# PLO_v1.net
KiCad netlist of a schematic drawn in EAGLE
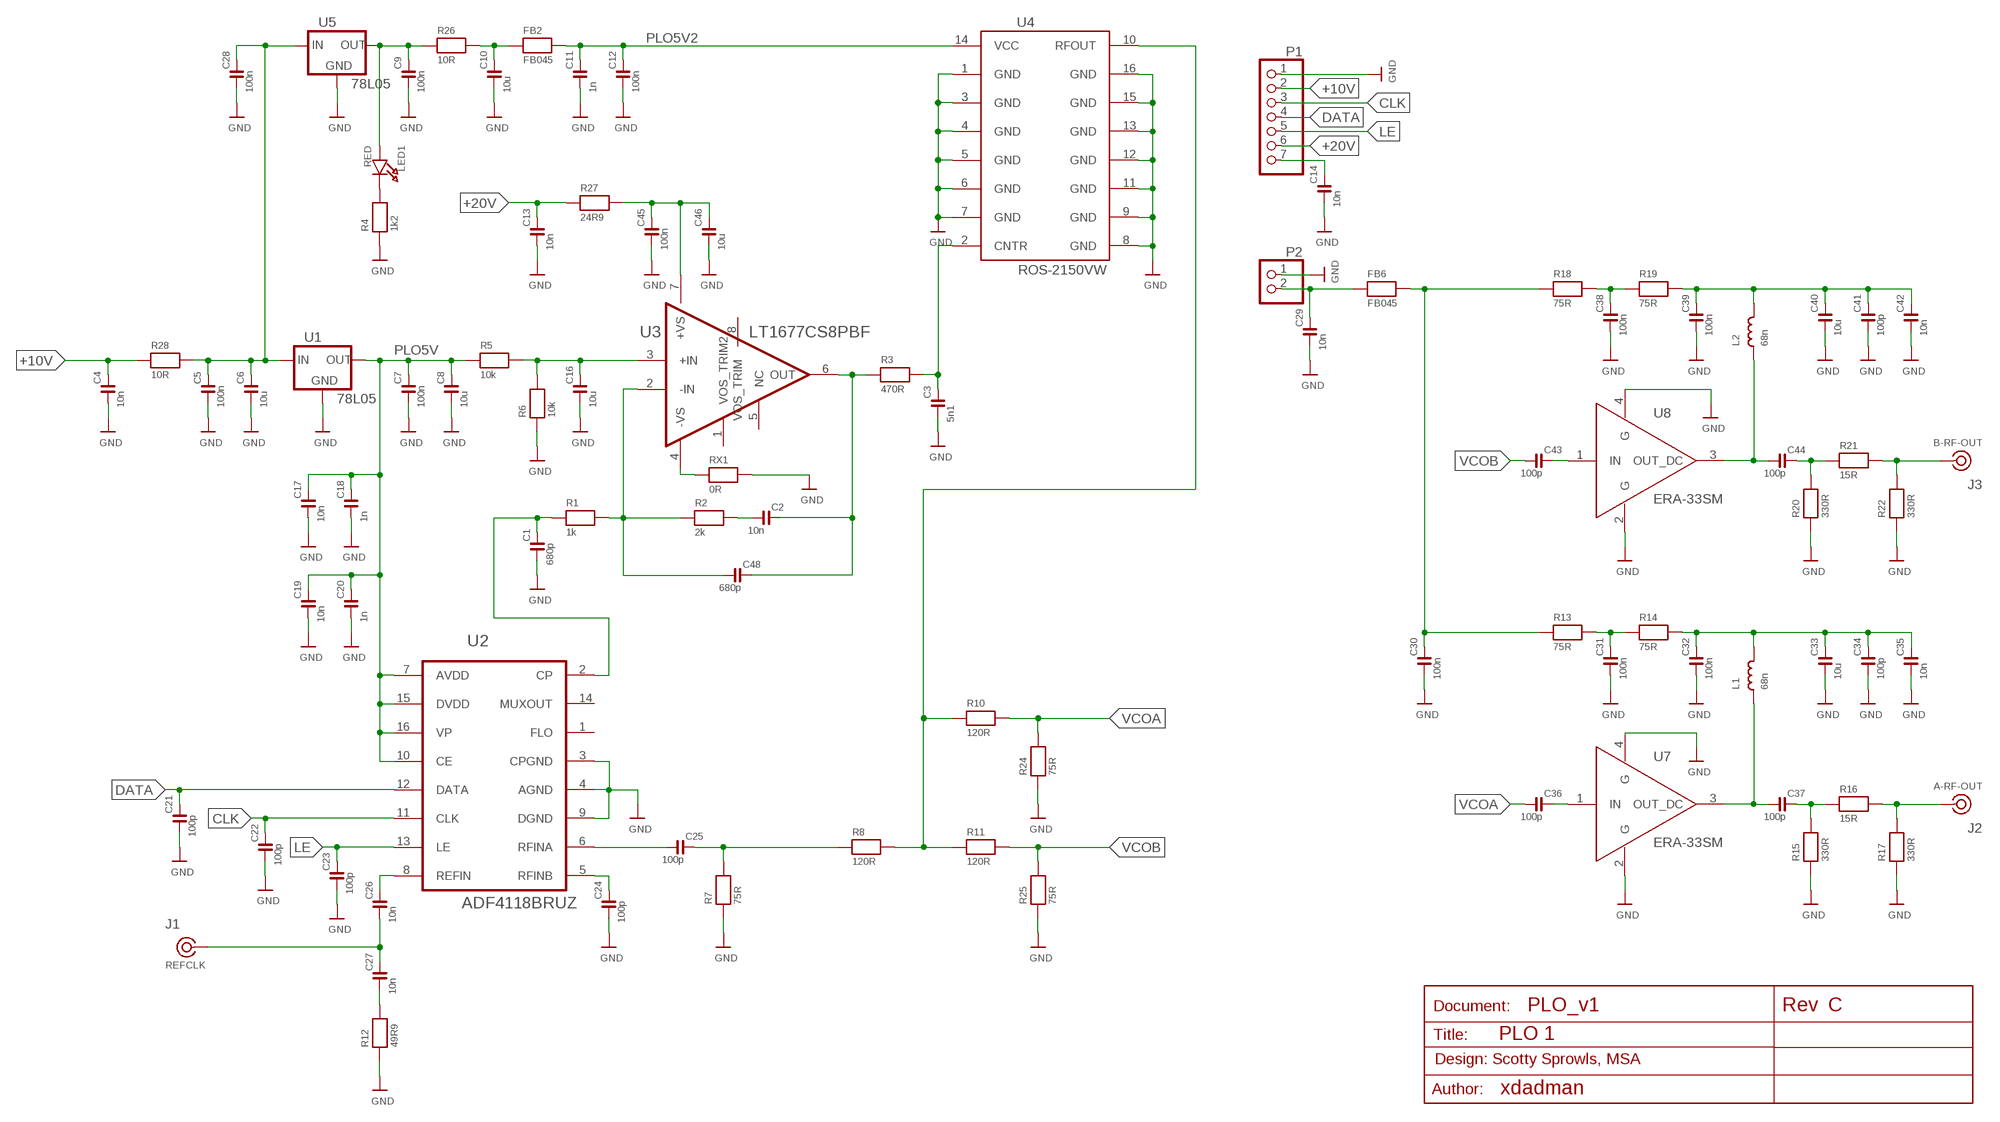
[diagram p0: schematic, sheet 1]

(export (version "E")
  (design (tool "Eeschema 10.0.6"))
  (components
    (comp (ref "C1")
      (value "680p")
      (footprint "eagle-import:C0805")
      (libsource (lib "eagle-import") (part "C0805680P"))
    )
    (comp (ref "C2")
      (value "10n")
      (footprint "eagle-import:C0805")
      (libsource (lib "eagle-import") (part "C080510N"))
    )
    (comp (ref "C3")
      (value "5n1")
      (footprint "eagle-import:C0805")
      (libsource (lib "eagle-import") (part "C08055N1"))
    )
    (comp (ref "C4")
      (value "10n")
      (footprint "eagle-import:C0805")
      (libsource (lib "eagle-import") (part "C080510N"))
    )
    (comp (ref "C5")
      (value "100n")
      (footprint "eagle-import:C0805")
      (libsource (lib "eagle-import") (part "C0805100N"))
    )
    (comp (ref "C6")
      (value "10u")
      (footprint "eagle-import:C1206")
      (libsource (lib "eagle-import") (part "CC120610U"))
    )
    (comp (ref "C7")
      (value "100n")
      (footprint "eagle-import:C0805")
      (libsource (lib "eagle-import") (part "C0805100N"))
    )
    (comp (ref "C8")
      (value "10u")
      (footprint "eagle-import:C1206")
      (libsource (lib "eagle-import") (part "CC120610U"))
    )
    (comp (ref "C9")
      (value "100n")
      (footprint "eagle-import:C0805")
      (libsource (lib "eagle-import") (part "C0805100N"))
    )
    (comp (ref "C10")
      (value "10u")
      (footprint "eagle-import:C1206")
      (libsource (lib "eagle-import") (part "CC120610U"))
    )
    (comp (ref "C11")
      (value "1n")
      (footprint "eagle-import:C0805")
      (libsource (lib "eagle-import") (part "C08051N"))
    )
    (comp (ref "C12")
      (value "100n")
      (footprint "eagle-import:C0805")
      (libsource (lib "eagle-import") (part "C0805100N"))
    )
    (comp (ref "C13")
      (value "10n")
      (footprint "eagle-import:C0805")
      (libsource (lib "eagle-import") (part "C080510N"))
    )
    (comp (ref "C14")
      (value "10n")
      (footprint "eagle-import:C0805")
      (libsource (lib "eagle-import") (part "C080510N"))
    )
    (comp (ref "C16")
      (value "10u")
      (footprint "eagle-import:C1206")
      (libsource (lib "eagle-import") (part "CC120610U"))
    )
    (comp (ref "C17")
      (value "10n")
      (footprint "eagle-import:C0805")
      (libsource (lib "eagle-import") (part "C080510N"))
    )
    (comp (ref "C18")
      (value "1n")
      (footprint "eagle-import:C0805")
      (libsource (lib "eagle-import") (part "C08051N"))
    )
    (comp (ref "C19")
      (value "10n")
      (footprint "eagle-import:C0805")
      (libsource (lib "eagle-import") (part "C080510N"))
    )
    (comp (ref "C20")
      (value "1n")
      (footprint "eagle-import:C0805")
      (libsource (lib "eagle-import") (part "C08051N"))
    )
    (comp (ref "C21")
      (value "100p")
      (footprint "eagle-import:C0805")
      (libsource (lib "eagle-import") (part "C0805100P"))
    )
    (comp (ref "C22")
      (value "100p")
      (footprint "eagle-import:C0805")
      (libsource (lib "eagle-import") (part "C0805100P"))
    )
    (comp (ref "C23")
      (value "100p")
      (footprint "eagle-import:C0805")
      (libsource (lib "eagle-import") (part "C0805100P"))
    )
    (comp (ref "C24")
      (value "100p")
      (footprint "eagle-import:C0805")
      (libsource (lib "eagle-import") (part "C0805100P"))
    )
    (comp (ref "C25")
      (value "100p")
      (footprint "eagle-import:C0805")
      (libsource (lib "eagle-import") (part "C0805100P"))
    )
    (comp (ref "C26")
      (value "10n")
      (footprint "eagle-import:C0805")
      (libsource (lib "eagle-import") (part "C080510N"))
    )
    (comp (ref "C27")
      (value "10n")
      (footprint "eagle-import:C0805")
      (libsource (lib "eagle-import") (part "C080510N"))
    )
    (comp (ref "C28")
      (value "100n")
      (footprint "eagle-import:C0805")
      (libsource (lib "eagle-import") (part "C0805100N"))
    )
    (comp (ref "C29")
      (value "10n")
      (footprint "eagle-import:C0805")
      (libsource (lib "eagle-import") (part "C080510N"))
    )
    (comp (ref "C30")
      (value "100n")
      (footprint "eagle-import:C0805")
      (libsource (lib "eagle-import") (part "C0805100N"))
    )
    (comp (ref "C31")
      (value "100n")
      (footprint "eagle-import:C0805")
      (libsource (lib "eagle-import") (part "C0805100N"))
    )
    (comp (ref "C32")
      (value "100n")
      (footprint "eagle-import:C0805")
      (libsource (lib "eagle-import") (part "C0805100N"))
    )
    (comp (ref "C33")
      (value "10u")
      (footprint "eagle-import:C1206")
      (libsource (lib "eagle-import") (part "CC120610U"))
    )
    (comp (ref "C34")
      (value "100p")
      (footprint "eagle-import:C0805")
      (libsource (lib "eagle-import") (part "C0805100P"))
    )
    (comp (ref "C35")
      (value "10n")
      (footprint "eagle-import:C0805")
      (libsource (lib "eagle-import") (part "C080510N"))
    )
    (comp (ref "C36")
      (value "100p")
      (footprint "eagle-import:C0805")
      (libsource (lib "eagle-import") (part "C0805100P"))
    )
    (comp (ref "C37")
      (value "100p")
      (footprint "eagle-import:C0805")
      (libsource (lib "eagle-import") (part "C0805100P"))
    )
    (comp (ref "C38")
      (value "100n")
      (footprint "eagle-import:C0805")
      (libsource (lib "eagle-import") (part "C0805100N"))
    )
    (comp (ref "C39")
      (value "100n")
      (footprint "eagle-import:C0805")
      (libsource (lib "eagle-import") (part "C0805100N"))
    )
    (comp (ref "C40")
      (value "10u")
      (footprint "eagle-import:C1206")
      (libsource (lib "eagle-import") (part "CC120610U"))
    )
    (comp (ref "C41")
      (value "100p")
      (footprint "eagle-import:C0805")
      (libsource (lib "eagle-import") (part "C0805100P"))
    )
    (comp (ref "C42")
      (value "10n")
      (footprint "eagle-import:C0805")
      (libsource (lib "eagle-import") (part "C080510N"))
    )
    (comp (ref "C43")
      (value "100p")
      (footprint "eagle-import:C0805")
      (libsource (lib "eagle-import") (part "C0805100P"))
    )
    (comp (ref "C44")
      (value "100p")
      (footprint "eagle-import:C0805")
      (libsource (lib "eagle-import") (part "C0805100P"))
    )
    (comp (ref "C45")
      (value "100n")
      (footprint "eagle-import:C0805")
      (libsource (lib "eagle-import") (part "C0805100N"))
    )
    (comp (ref "C46")
      (value "10u")
      (footprint "eagle-import:C1206")
      (libsource (lib "eagle-import") (part "CC120610U"))
    )
    (comp (ref "C48")
      (value "680p")
      (footprint "eagle-import:C0805")
      (libsource (lib "eagle-import") (part "C0805680P"))
    )
    (comp (ref "FB2")
      (value "FB045")
      (footprint "eagle-import:R0805_SPC")
      (libsource (lib "eagle-import") (part "R0805FB045SPC"))
    )
    (comp (ref "FB6")
      (value "FB045")
      (footprint "eagle-import:R0805")
      (libsource (lib "eagle-import") (part "R0805FB045"))
    )
    (comp (ref "J1")
      (value "REFCLK")
      (footprint "eagle-import:SLIM_COAX_PAD")
      (libsource (lib "eagle-import") (part "COAX"))
    )
    (comp (ref "J2")
      (value "A-RF-OUT")
      (footprint "eagle-import:SLIM_COAX_PAD")
      (libsource (lib "eagle-import") (part "COAX"))
    )
    (comp (ref "J3")
      (value "B-RF-OUT")
      (footprint "eagle-import:SLIM_COAX_PAD")
      (libsource (lib "eagle-import") (part "COAX"))
    )
    (comp (ref "L1")
      (value "68n")
      (footprint "eagle-import:0603-MINI")
      (libsource (lib "eagle-import") (part "L060368N"))
    )
    (comp (ref "L2")
      (value "68n")
      (footprint "eagle-import:0603-MINI")
      (libsource (lib "eagle-import") (part "L060368N"))
    )
    (comp (ref "LED1")
      (value "RED")
      (footprint "eagle-import:CHIPLED_0603")
      (libsource (lib "eagle-import") (part "LED_0603_RED0603"))
    )
    (comp (ref "P1")
      (value "PINHD-1X7")
      (footprint "eagle-import:1X07")
      (libsource (lib "eagle-import") (part "PINHD-1X7"))
    )
    (comp (ref "P2")
      (value "PINHD-1X2")
      (footprint "eagle-import:1X02")
      (libsource (lib "eagle-import") (part "PINHD-1X2"))
    )
    (comp (ref "R1")
      (value "1k")
      (footprint "eagle-import:R0805")
      (libsource (lib "eagle-import") (part "R08051K"))
    )
    (comp (ref "R2")
      (value "2k")
      (footprint "eagle-import:C0805")
      (libsource (lib "eagle-import") (part "R08052K"))
    )
    (comp (ref "R3")
      (value "470R")
      (footprint "eagle-import:R0805")
      (libsource (lib "eagle-import") (part "R0805470R"))
    )
    (comp (ref "R4")
      (value "1k2")
      (footprint "eagle-import:R0805")
      (libsource (lib "eagle-import") (part "R08051K2"))
    )
    (comp (ref "R5")
      (value "10k")
      (footprint "eagle-import:R0805")
      (libsource (lib "eagle-import") (part "R080510K"))
    )
    (comp (ref "R6")
      (value "10k")
      (footprint "eagle-import:R0805")
      (libsource (lib "eagle-import") (part "R080510K"))
    )
    (comp (ref "R7")
      (value "75R")
      (footprint "eagle-import:R0805")
      (libsource (lib "eagle-import") (part "R080575R"))
    )
    (comp (ref "R8")
      (value "120R")
      (footprint "eagle-import:R0805")
      (libsource (lib "eagle-import") (part "R0805120R"))
    )
    (comp (ref "R10")
      (value "120R")
      (footprint "eagle-import:R0805")
      (libsource (lib "eagle-import") (part "R0805120R"))
    )
    (comp (ref "R11")
      (value "120R")
      (footprint "eagle-import:R0805")
      (libsource (lib "eagle-import") (part "R0805120R"))
    )
    (comp (ref "R12")
      (value "49R9")
      (footprint "eagle-import:R0805")
      (libsource (lib "eagle-import") (part "R080549R9"))
    )
    (comp (ref "R13")
      (value "75R")
      (footprint "eagle-import:R0805")
      (libsource (lib "eagle-import") (part "R080575R"))
    )
    (comp (ref "R14")
      (value "75R")
      (footprint "eagle-import:R0805")
      (libsource (lib "eagle-import") (part "R080575R"))
    )
    (comp (ref "R15")
      (value "330R")
      (footprint "eagle-import:R0805")
      (libsource (lib "eagle-import") (part "R0805330R"))
    )
    (comp (ref "R16")
      (value "15R")
      (footprint "eagle-import:0805")
      (libsource (lib "eagle-import") (part "R080515R"))
    )
    (comp (ref "R17")
      (value "330R")
      (footprint "eagle-import:R0805")
      (libsource (lib "eagle-import") (part "R0805330R"))
    )
    (comp (ref "R18")
      (value "75R")
      (footprint "eagle-import:R0805")
      (libsource (lib "eagle-import") (part "R080575R"))
    )
    (comp (ref "R19")
      (value "75R")
      (footprint "eagle-import:R0805")
      (libsource (lib "eagle-import") (part "R080575R"))
    )
    (comp (ref "R20")
      (value "330R")
      (footprint "eagle-import:R0805")
      (libsource (lib "eagle-import") (part "R0805330R"))
    )
    (comp (ref "R21")
      (value "15R")
      (footprint "eagle-import:0805")
      (libsource (lib "eagle-import") (part "R080515R"))
    )
    (comp (ref "R22")
      (value "330R")
      (footprint "eagle-import:R0805")
      (libsource (lib "eagle-import") (part "R0805330R"))
    )
    (comp (ref "R24")
      (value "75R")
      (footprint "eagle-import:R0805")
      (libsource (lib "eagle-import") (part "R080575R"))
    )
    (comp (ref "R25")
      (value "75R")
      (footprint "eagle-import:R0805")
      (libsource (lib "eagle-import") (part "R080575R"))
    )
    (comp (ref "R26")
      (value "10R")
      (footprint "eagle-import:R0805")
      (libsource (lib "eagle-import") (part "R080510R"))
    )
    (comp (ref "R27")
      (value "24R9")
      (footprint "eagle-import:R0805")
      (libsource (lib "eagle-import") (part "R080524R9"))
    )
    (comp (ref "R28")
      (value "10R")
      (footprint "eagle-import:R0805")
      (libsource (lib "eagle-import") (part "R080510R"))
    )
    (comp (ref "RX1")
      (value "0R")
      (footprint "eagle-import:R0805")
      (libsource (lib "eagle-import") (part "R08050R"))
    )
    (comp (ref "U1")
      (value "78L05")
      (footprint "eagle-import:SOT89")
      (libsource (lib "eagle-import") (part "78MXXL78L05"))
    )
    (comp (ref "U2")
      (value "ADF4118BRUZ")
      (footprint "eagle-import:SOIC65P640X120-16N")
      (libsource (lib "eagle-import") (part "ADF4118BRUZ"))
    )
    (comp (ref "U3")
      (value "LT1677CS8PBF")
      (footprint "eagle-import:SOIC127P600X175-8N_JDA2")
      (fields (field (name "MPN") "LT1677CS8#PBF"))
      (libsource (lib "eagle-import") (part "LT1677CS8PBF"))
    )
    (comp (ref "U4")
      (value "ROS-2150VW")
      (footprint "eagle-import:ROS-2150VW")
      (libsource (lib "eagle-import") (part "ROS-2150VW"))
    )
    (comp (ref "U5")
      (value "78L05")
      (footprint "eagle-import:SOT89")
      (libsource (lib "eagle-import") (part "78MXXL78L05"))
    )
    (comp (ref "U7")
      (value "ERA-33SM")
      (footprint "eagle-import:WW107")
      (libsource (lib "eagle-import") (part "ERA-33SM"))
    )
    (comp (ref "U8")
      (value "ERA-33SM")
      (footprint "eagle-import:WW107")
      (libsource (lib "eagle-import") (part "ERA-33SM"))
    )
  )
  (nets
    (net (code "1") (name "+10V") (class "Default")
      (node (ref "C4") (pin "2") (pinfunction "2_2") (pintype "passive"))
      (node (ref "P1") (pin "2") (pinfunction "2_2") (pintype "passive"))
      (node (ref "R28") (pin "1") (pinfunction "1_1") (pintype "passive"))
    )
    (net (code "2") (name "+20V") (class "Default")
      (node (ref "C13") (pin "2") (pinfunction "2_2") (pintype "passive"))
      (node (ref "P1") (pin "6") (pinfunction "6_6") (pintype "passive"))
      (node (ref "R27") (pin "1") (pinfunction "1_1") (pintype "passive"))
    )
    (net (code "3") (name "/PLO5V") (class "Default")
      (node (ref "C17") (pin "2") (pinfunction "2_2") (pintype "passive"))
      (node (ref "C18") (pin "2") (pinfunction "2_2") (pintype "passive"))
      (node (ref "C19") (pin "2") (pinfunction "2_2") (pintype "passive"))
      (node (ref "C20") (pin "2") (pinfunction "2_2") (pintype "passive"))
      (node (ref "C7") (pin "2") (pinfunction "2_2") (pintype "passive"))
      (node (ref "C8") (pin "2") (pinfunction "2_2") (pintype "passive"))
      (node (ref "R5") (pin "1") (pinfunction "1_1") (pintype "passive"))
      (node (ref "U1") (pin "1") (pinfunction "OUT_1") (pintype "passive"))
      (node (ref "U2") (pin "10") (pinfunction "CE_10") (pintype "input"))
      (node (ref "U2") (pin "15") (pinfunction "DVDD_15") (pintype "power_in"))
      (node (ref "U2") (pin "16") (pinfunction "VP_16") (pintype "power_in"))
      (node (ref "U2") (pin "7") (pinfunction "AVDD_7") (pintype "power_in"))
    )
    (net (code "4") (name "/PLO5V2") (class "Default")
      (node (ref "C11") (pin "2") (pinfunction "2_2") (pintype "passive"))
      (node (ref "C12") (pin "2") (pinfunction "2_2") (pintype "passive"))
      (node (ref "FB2") (pin "2") (pinfunction "2_2") (pintype "passive"))
      (node (ref "U4") (pin "14") (pinfunction "VCC_14") (pintype "bidirectional"))
    )
    (net (code "5") (name "CLK") (class "Default")
      (node (ref "C22") (pin "2") (pinfunction "2_2") (pintype "passive"))
      (node (ref "P1") (pin "3") (pinfunction "3_3") (pintype "passive"))
      (node (ref "U2") (pin "11") (pinfunction "CLK_11") (pintype "input"))
    )
    (net (code "6") (name "DATA") (class "Default")
      (node (ref "C21") (pin "2") (pinfunction "2_2") (pintype "passive"))
      (node (ref "P1") (pin "4") (pinfunction "4_4") (pintype "passive"))
      (node (ref "U2") (pin "12") (pinfunction "DATA_12") (pintype "input"))
    )
    (net (code "7") (name "GND") (class "Default")
      (node (ref "C1") (pin "1") (pinfunction "1_1") (pintype "passive"))
      (node (ref "C10") (pin "1") (pinfunction "1_1") (pintype "passive"))
      (node (ref "C11") (pin "1") (pinfunction "1_1") (pintype "passive"))
      (node (ref "C12") (pin "1") (pinfunction "1_1") (pintype "passive"))
      (node (ref "C13") (pin "1") (pinfunction "1_1") (pintype "passive"))
      (node (ref "C14") (pin "1") (pinfunction "1_1") (pintype "passive"))
      (node (ref "C16") (pin "1") (pinfunction "1_1") (pintype "passive"))
      (node (ref "C17") (pin "1") (pinfunction "1_1") (pintype "passive"))
      (node (ref "C18") (pin "1") (pinfunction "1_1") (pintype "passive"))
      (node (ref "C19") (pin "1") (pinfunction "1_1") (pintype "passive"))
      (node (ref "C20") (pin "1") (pinfunction "1_1") (pintype "passive"))
      (node (ref "C21") (pin "1") (pinfunction "1_1") (pintype "passive"))
      (node (ref "C22") (pin "1") (pinfunction "1_1") (pintype "passive"))
      (node (ref "C23") (pin "1") (pinfunction "1_1") (pintype "passive"))
      (node (ref "C24") (pin "1") (pinfunction "1_1") (pintype "passive"))
      (node (ref "C28") (pin "1") (pinfunction "1_1") (pintype "passive"))
      (node (ref "C29") (pin "1") (pinfunction "1_1") (pintype "passive"))
      (node (ref "C3") (pin "1") (pinfunction "1_1") (pintype "passive"))
      (node (ref "C30") (pin "1") (pinfunction "1_1") (pintype "passive"))
      (node (ref "C31") (pin "1") (pinfunction "1_1") (pintype "passive"))
      (node (ref "C32") (pin "1") (pinfunction "1_1") (pintype "passive"))
      (node (ref "C33") (pin "1") (pinfunction "1_1") (pintype "passive"))
      (node (ref "C34") (pin "1") (pinfunction "1_1") (pintype "passive"))
      (node (ref "C35") (pin "1") (pinfunction "1_1") (pintype "passive"))
      (node (ref "C38") (pin "1") (pinfunction "1_1") (pintype "passive"))
      (node (ref "C39") (pin "1") (pinfunction "1_1") (pintype "passive"))
      (node (ref "C4") (pin "1") (pinfunction "1_1") (pintype "passive"))
      (node (ref "C40") (pin "1") (pinfunction "1_1") (pintype "passive"))
      (node (ref "C41") (pin "1") (pinfunction "1_1") (pintype "passive"))
      (node (ref "C42") (pin "1") (pinfunction "1_1") (pintype "passive"))
      (node (ref "C45") (pin "1") (pinfunction "1_1") (pintype "passive"))
      (node (ref "C46") (pin "1") (pinfunction "1_1") (pintype "passive"))
      (node (ref "C5") (pin "1") (pinfunction "1_1") (pintype "passive"))
      (node (ref "C6") (pin "1") (pinfunction "1_1") (pintype "passive"))
      (node (ref "C7") (pin "1") (pinfunction "1_1") (pintype "passive"))
      (node (ref "C8") (pin "1") (pinfunction "1_1") (pintype "passive"))
      (node (ref "C9") (pin "1") (pinfunction "1_1") (pintype "passive"))
      (node (ref "P1") (pin "1") (pinfunction "1_1") (pintype "passive"))
      (node (ref "P2") (pin "1") (pinfunction "1_1") (pintype "passive"))
      (node (ref "R12") (pin "1") (pinfunction "1_1") (pintype "passive"))
      (node (ref "R15") (pin "1") (pinfunction "1_1") (pintype "passive"))
      (node (ref "R17") (pin "1") (pinfunction "1_1") (pintype "passive"))
      (node (ref "R20") (pin "1") (pinfunction "1_1") (pintype "passive"))
      (node (ref "R22") (pin "1") (pinfunction "1_1") (pintype "passive"))
      (node (ref "R24") (pin "1") (pinfunction "1_1") (pintype "passive"))
      (node (ref "R25") (pin "1") (pinfunction "1_1") (pintype "passive"))
      (node (ref "R4") (pin "1") (pinfunction "1_1") (pintype "passive"))
      (node (ref "R6") (pin "1") (pinfunction "1_1") (pintype "passive"))
      (node (ref "R7") (pin "1") (pinfunction "1_1") (pintype "passive"))
      (node (ref "RX1") (pin "2") (pinfunction "2_2") (pintype "passive"))
      (node (ref "U1") (pin "2") (pinfunction "GND_2") (pintype "input"))
      (node (ref "U1") (pin "4") (pinfunction "GND_4") (pintype "input"))
      (node (ref "U2") (pin "3") (pinfunction "CPGND_3") (pintype "passive"))
      (node (ref "U2") (pin "4") (pinfunction "AGND_4") (pintype "passive"))
      (node (ref "U2") (pin "9") (pinfunction "DGND_9") (pintype "passive"))
      (node (ref "U4") (pin "1") (pinfunction "GND_1") (pintype "bidirectional"))
      (node (ref "U4") (pin "11") (pinfunction "GND_11") (pintype "bidirectional"))
      (node (ref "U4") (pin "12") (pinfunction "GND_12") (pintype "bidirectional"))
      (node (ref "U4") (pin "13") (pinfunction "GND_13") (pintype "bidirectional"))
      (node (ref "U4") (pin "15") (pinfunction "GND_15") (pintype "bidirectional"))
      (node (ref "U4") (pin "16") (pinfunction "GND_16") (pintype "bidirectional"))
      (node (ref "U4") (pin "3") (pinfunction "GND_3") (pintype "bidirectional"))
      (node (ref "U4") (pin "4") (pinfunction "GND_4") (pintype "bidirectional"))
      (node (ref "U4") (pin "5") (pinfunction "GND_5") (pintype "bidirectional"))
      (node (ref "U4") (pin "6") (pinfunction "GND_6") (pintype "bidirectional"))
      (node (ref "U4") (pin "7") (pinfunction "GND_7") (pintype "bidirectional"))
      (node (ref "U4") (pin "8") (pinfunction "GND_8") (pintype "bidirectional"))
      (node (ref "U4") (pin "9") (pinfunction "GND_9") (pintype "bidirectional"))
      (node (ref "U5") (pin "2") (pinfunction "GND_2") (pintype "input"))
      (node (ref "U5") (pin "4") (pinfunction "GND_4") (pintype "input"))
      (node (ref "U7") (pin "2") (pinfunction "G_2") (pintype "bidirectional"))
      (node (ref "U7") (pin "4") (pinfunction "G_4") (pintype "bidirectional"))
      (node (ref "U8") (pin "2") (pinfunction "G_2") (pintype "bidirectional"))
      (node (ref "U8") (pin "4") (pinfunction "G_4") (pintype "bidirectional"))
    )
    (net (code "8") (name "LE") (class "Default")
      (node (ref "C23") (pin "2") (pinfunction "2_2") (pintype "passive"))
      (node (ref "P1") (pin "5") (pinfunction "5_5") (pintype "passive"))
      (node (ref "U2") (pin "13") (pinfunction "LE_13") (pintype "input"))
    )
    (net (code "9") (name "Net-(C2-Pad1)") (class "Default")
      (node (ref "C2") (pin "1") (pinfunction "1_1") (pintype "passive"))
      (node (ref "R2") (pin "2") (pinfunction "2_2") (pintype "passive"))
    )
    (net (code "10") (name "Net-(C10-Pad2)") (class "Default")
      (node (ref "C10") (pin "2") (pinfunction "2_2") (pintype "passive"))
      (node (ref "FB2") (pin "1") (pinfunction "1_1") (pintype "passive"))
      (node (ref "R26") (pin "2") (pinfunction "2_2") (pintype "passive"))
    )
    (net (code "11") (name "Net-(C14-Pad2)") (class "Default")
      (node (ref "C14") (pin "2") (pinfunction "2_2") (pintype "passive"))
      (node (ref "P1") (pin "7") (pinfunction "7_7") (pintype "passive"))
    )
    (net (code "12") (name "Net-(C25-Pad2)") (class "Default")
      (node (ref "C25") (pin "2") (pinfunction "2_2") (pintype "passive"))
      (node (ref "R7") (pin "2") (pinfunction "2_2") (pintype "passive"))
      (node (ref "R8") (pin "1") (pinfunction "1_1") (pintype "passive"))
    )
    (net (code "13") (name "Net-(C27-Pad1)") (class "Default")
      (node (ref "C27") (pin "1") (pinfunction "1_1") (pintype "passive"))
      (node (ref "R12") (pin "2") (pinfunction "2_2") (pintype "passive"))
    )
    (net (code "14") (name "Net-(C29-Pad2)") (class "Default")
      (node (ref "C29") (pin "2") (pinfunction "2_2") (pintype "passive"))
      (node (ref "FB6") (pin "1") (pinfunction "1_1") (pintype "passive"))
      (node (ref "P2") (pin "2") (pinfunction "2_2") (pintype "passive"))
    )
    (net (code "15") (name "Net-(C30-Pad2)") (class "Default")
      (node (ref "C30") (pin "2") (pinfunction "2_2") (pintype "passive"))
      (node (ref "FB6") (pin "2") (pinfunction "2_2") (pintype "passive"))
      (node (ref "R13") (pin "1") (pinfunction "1_1") (pintype "passive"))
      (node (ref "R18") (pin "1") (pinfunction "1_1") (pintype "passive"))
    )
    (net (code "16") (name "Net-(C31-Pad2)") (class "Default")
      (node (ref "C31") (pin "2") (pinfunction "2_2") (pintype "passive"))
      (node (ref "R13") (pin "2") (pinfunction "2_2") (pintype "passive"))
      (node (ref "R14") (pin "1") (pinfunction "1_1") (pintype "passive"))
    )
    (net (code "17") (name "Net-(C32-Pad2)") (class "Default")
      (node (ref "C32") (pin "2") (pinfunction "2_2") (pintype "passive"))
      (node (ref "C33") (pin "2") (pinfunction "2_2") (pintype "passive"))
      (node (ref "C34") (pin "2") (pinfunction "2_2") (pintype "passive"))
      (node (ref "C35") (pin "2") (pinfunction "2_2") (pintype "passive"))
      (node (ref "L1") (pin "2") (pinfunction "2_2") (pintype "passive"))
      (node (ref "R14") (pin "2") (pinfunction "2_2") (pintype "passive"))
    )
    (net (code "18") (name "Net-(C37-Pad2)") (class "Default")
      (node (ref "C37") (pin "2") (pinfunction "2_2") (pintype "passive"))
      (node (ref "R15") (pin "2") (pinfunction "2_2") (pintype "passive"))
      (node (ref "R16") (pin "1") (pinfunction "1_1") (pintype "passive"))
    )
    (net (code "19") (name "Net-(C38-Pad2)") (class "Default")
      (node (ref "C38") (pin "2") (pinfunction "2_2") (pintype "passive"))
      (node (ref "R18") (pin "2") (pinfunction "2_2") (pintype "passive"))
      (node (ref "R19") (pin "1") (pinfunction "1_1") (pintype "passive"))
    )
    (net (code "20") (name "Net-(C39-Pad2)") (class "Default")
      (node (ref "C39") (pin "2") (pinfunction "2_2") (pintype "passive"))
      (node (ref "C40") (pin "2") (pinfunction "2_2") (pintype "passive"))
      (node (ref "C41") (pin "2") (pinfunction "2_2") (pintype "passive"))
      (node (ref "C42") (pin "2") (pinfunction "2_2") (pintype "passive"))
      (node (ref "L2") (pin "2") (pinfunction "2_2") (pintype "passive"))
      (node (ref "R19") (pin "2") (pinfunction "2_2") (pintype "passive"))
    )
    (net (code "21") (name "Net-(C44-Pad2)") (class "Default")
      (node (ref "C44") (pin "2") (pinfunction "2_2") (pintype "passive"))
      (node (ref "R20") (pin "2") (pinfunction "2_2") (pintype "passive"))
      (node (ref "R21") (pin "1") (pinfunction "1_1") (pintype "passive"))
    )
    (net (code "22") (name "Net-(J1A-1)") (class "Default")
      (node (ref "C26") (pin "1") (pinfunction "1_1") (pintype "passive"))
      (node (ref "C27") (pin "2") (pinfunction "2_2") (pintype "passive"))
      (node (ref "J1") (pin "SIG") (pinfunction "1_SIG") (pintype "passive"))
    )
    (net (code "23") (name "Net-(J2A-1)") (class "Default")
      (node (ref "J2") (pin "SIG") (pinfunction "1_SIG") (pintype "passive"))
      (node (ref "R16") (pin "2") (pinfunction "2_2") (pintype "passive"))
      (node (ref "R17") (pin "2") (pinfunction "2_2") (pintype "passive"))
    )
    (net (code "24") (name "Net-(J3A-1)") (class "Default")
      (node (ref "J3") (pin "SIG") (pinfunction "1_SIG") (pintype "passive"))
      (node (ref "R21") (pin "2") (pinfunction "2_2") (pintype "passive"))
      (node (ref "R22") (pin "2") (pinfunction "2_2") (pintype "passive"))
    )
    (net (code "25") (name "Net-(LED1-PadC)") (class "Default")
      (node (ref "LED1") (pin "C") (pinfunction "C_C") (pintype "passive"))
      (node (ref "R4") (pin "2") (pinfunction "2_2") (pintype "passive"))
    )
    (net (code "26") (name "Net-(U1-IN)") (class "Default")
      (node (ref "C28") (pin "2") (pinfunction "2_2") (pintype "passive"))
      (node (ref "C5") (pin "2") (pinfunction "2_2") (pintype "passive"))
      (node (ref "C6") (pin "2") (pinfunction "2_2") (pintype "passive"))
      (node (ref "R28") (pin "2") (pinfunction "2_2") (pintype "passive"))
      (node (ref "U1") (pin "3") (pinfunction "IN_3") (pintype "input"))
      (node (ref "U5") (pin "3") (pinfunction "IN_3") (pintype "input"))
    )
    (net (code "27") (name "Net-(U2-CP)") (class "Default")
      (node (ref "C1") (pin "2") (pinfunction "2_2") (pintype "passive"))
      (node (ref "R1") (pin "1") (pinfunction "1_1") (pintype "passive"))
      (node (ref "U2") (pin "2") (pinfunction "CP_2") (pintype "output"))
    )
    (net (code "28") (name "Net-(U2-REFIN)") (class "Default")
      (node (ref "C26") (pin "2") (pinfunction "2_2") (pintype "passive"))
      (node (ref "U2") (pin "8") (pinfunction "REFIN_8") (pintype "input"))
    )
    (net (code "29") (name "Net-(U2-RFINA)") (class "Default")
      (node (ref "C25") (pin "1") (pinfunction "1_1") (pintype "passive"))
      (node (ref "U2") (pin "6") (pinfunction "RFINA_6") (pintype "input"))
    )
    (net (code "30") (name "Net-(U2-RFINB)") (class "Default")
      (node (ref "C24") (pin "2") (pinfunction "2_2") (pintype "passive"))
      (node (ref "U2") (pin "5") (pinfunction "RFINB_5") (pintype "input"))
    )
    (net (code "31") (name "Net-(U3-+IN)") (class "Default")
      (node (ref "C16") (pin "2") (pinfunction "2_2") (pintype "passive"))
      (node (ref "R5") (pin "2") (pinfunction "2_2") (pintype "passive"))
      (node (ref "R6") (pin "2") (pinfunction "2_2") (pintype "passive"))
      (node (ref "U3") (pin "3") (pinfunction "+IN_3") (pintype "input"))
    )
    (net (code "32") (name "Net-(U3-+VS)") (class "Default")
      (node (ref "C45") (pin "2") (pinfunction "2_2") (pintype "passive"))
      (node (ref "C46") (pin "2") (pinfunction "2_2") (pintype "passive"))
      (node (ref "R27") (pin "2") (pinfunction "2_2") (pintype "passive"))
      (node (ref "U3") (pin "7") (pinfunction "+VS_7") (pintype "power_in"))
    )
    (net (code "33") (name "Net-(U3--IN)") (class "Default")
      (node (ref "C48") (pin "1") (pinfunction "1_1") (pintype "passive"))
      (node (ref "R1") (pin "2") (pinfunction "2_2") (pintype "passive"))
      (node (ref "R2") (pin "1") (pinfunction "1_1") (pintype "passive"))
      (node (ref "U3") (pin "2") (pinfunction "-IN_2") (pintype "input"))
    )
    (net (code "34") (name "Net-(U3--VS)") (class "Default")
      (node (ref "RX1") (pin "1") (pinfunction "1_1") (pintype "passive"))
      (node (ref "U3") (pin "4") (pinfunction "-VS_4") (pintype "power_in"))
    )
    (net (code "35") (name "Net-(U3-OUT)") (class "Default")
      (node (ref "C2") (pin "2") (pinfunction "2_2") (pintype "passive"))
      (node (ref "C48") (pin "2") (pinfunction "2_2") (pintype "passive"))
      (node (ref "R3") (pin "1") (pinfunction "1_1") (pintype "passive"))
      (node (ref "U3") (pin "6") (pinfunction "OUT_6") (pintype "output"))
    )
    (net (code "36") (name "Net-(U4-CNTR)") (class "Default")
      (node (ref "C3") (pin "2") (pinfunction "2_2") (pintype "passive"))
      (node (ref "R3") (pin "2") (pinfunction "2_2") (pintype "passive"))
      (node (ref "U4") (pin "2") (pinfunction "CNTR_2") (pintype "bidirectional"))
    )
    (net (code "37") (name "Net-(U4-RFOUT)") (class "Default")
      (node (ref "R10") (pin "1") (pinfunction "1_1") (pintype "passive"))
      (node (ref "R11") (pin "1") (pinfunction "1_1") (pintype "passive"))
      (node (ref "R8") (pin "2") (pinfunction "2_2") (pintype "passive"))
      (node (ref "U4") (pin "10") (pinfunction "RFOUT_10") (pintype "bidirectional"))
    )
    (net (code "38") (name "Net-(U5-OUT)") (class "Default")
      (node (ref "C9") (pin "2") (pinfunction "2_2") (pintype "passive"))
      (node (ref "LED1") (pin "A") (pinfunction "A_A") (pintype "passive"))
      (node (ref "R26") (pin "1") (pinfunction "1_1") (pintype "passive"))
      (node (ref "U5") (pin "1") (pinfunction "OUT_1") (pintype "passive"))
    )
    (net (code "39") (name "Net-(U7-IN)") (class "Default")
      (node (ref "C36") (pin "2") (pinfunction "2_2") (pintype "passive"))
      (node (ref "U7") (pin "1") (pinfunction "IN_1") (pintype "bidirectional"))
    )
    (net (code "40") (name "Net-(U7-OUT_DC)") (class "Default")
      (node (ref "C37") (pin "1") (pinfunction "1_1") (pintype "passive"))
      (node (ref "L1") (pin "1") (pinfunction "1_1") (pintype "passive"))
      (node (ref "U7") (pin "3") (pinfunction "OUT_DC_3") (pintype "bidirectional"))
    )
    (net (code "41") (name "Net-(U8-IN)") (class "Default")
      (node (ref "C43") (pin "2") (pinfunction "2_2") (pintype "passive"))
      (node (ref "U8") (pin "1") (pinfunction "IN_1") (pintype "bidirectional"))
    )
    (net (code "42") (name "Net-(U8-OUT_DC)") (class "Default")
      (node (ref "C44") (pin "1") (pinfunction "1_1") (pintype "passive"))
      (node (ref "L2") (pin "1") (pinfunction "1_1") (pintype "passive"))
      (node (ref "U8") (pin "3") (pinfunction "OUT_DC_3") (pintype "bidirectional"))
    )
    (net (code "43") (name "VCOA") (class "Default")
      (node (ref "C36") (pin "1") (pinfunction "1_1") (pintype "passive"))
      (node (ref "R10") (pin "2") (pinfunction "2_2") (pintype "passive"))
      (node (ref "R24") (pin "2") (pinfunction "2_2") (pintype "passive"))
    )
    (net (code "44") (name "VCOB") (class "Default")
      (node (ref "C43") (pin "1") (pinfunction "1_1") (pintype "passive"))
      (node (ref "R11") (pin "2") (pinfunction "2_2") (pintype "passive"))
      (node (ref "R25") (pin "2") (pinfunction "2_2") (pintype "passive"))
    )
    (net (code "45") (name "unconnected-(U2-FLO-Pad1)") (class "Default")
      (node (ref "U2") (pin "1") (pinfunction "FLO_1") (pintype "output"))
    )
    (net (code "46") (name "unconnected-(U2-MUXOUT-Pad14)") (class "Default")
      (node (ref "U2") (pin "14") (pinfunction "MUXOUT_14") (pintype "output"))
    )
    (net (code "47") (name "unconnected-(U3-NC-Pad5)") (class "Default")
      (node (ref "U3") (pin "5") (pinfunction "NC_5") (pintype "no_connect"))
    )
    (net (code "48") (name "unconnected-(U3-VOS_TRIM-Pad8)") (class "Default")
      (node (ref "U3") (pin "8") (pinfunction "VOS_TRIM_8") (pintype "passive"))
    )
    (net (code "49") (name "unconnected-(U3-VOS_TRIM2-Pad1)") (class "Default")
      (node (ref "U3") (pin "1") (pinfunction "VOS_TRIM2_1") (pintype "passive"))
    )
  )
)
